# Power.net
KiCad netlist of a schematic drawn in Altium Designer
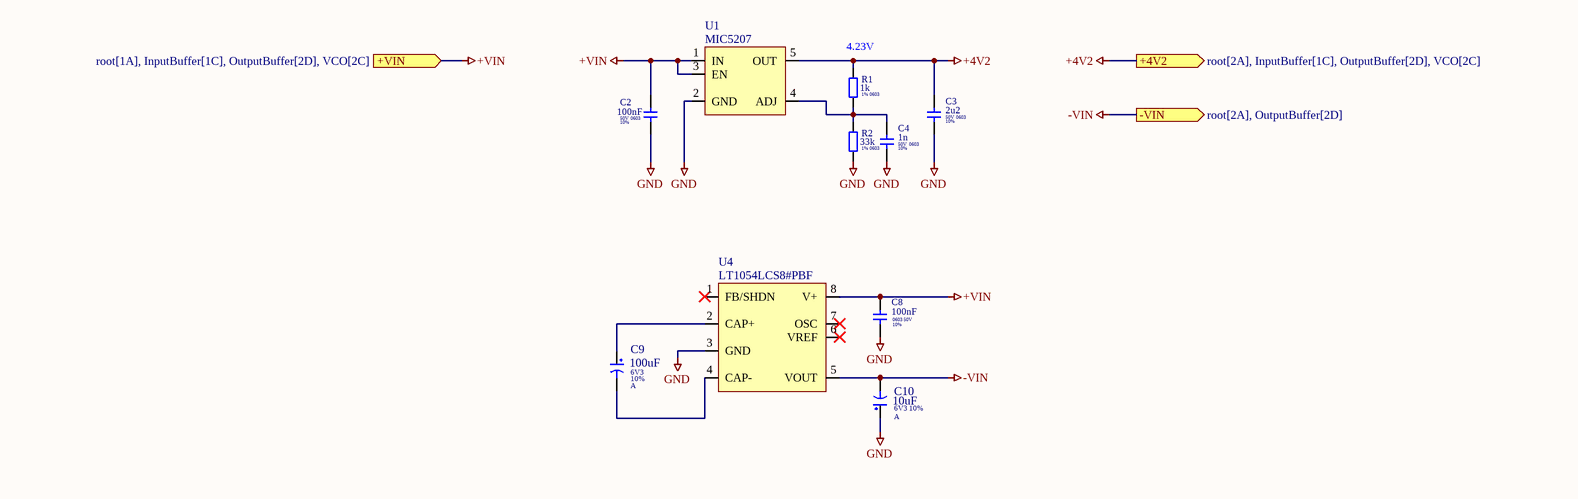
[diagram p0: Power.SchDoc]

(export (version "E")
  (design (tool "Eeschema 10.0.6"))
  (components
    (comp (ref "C2")
      (value "100nF")
      (footprint "CAPC1608X06M")
      (fields
        (field (name "VOLTAGE") "50V")
        (field (name "TOLERANT") "10%")
        (field (name "PACKAGE") "0603")
        (field (name "Comment") "100nF/50V")
      )
      (libsource (lib "Falcon-SchMain-Lib") (part "C"))
    )
    (comp (ref "C3")
      (value "2u2")
      (footprint "CAPC1608X06M")
      (fields
        (field (name "VOLTAGE") "50V")
        (field (name "TOLERANT") "10%")
        (field (name "PACKAGE") "0603")
        (field (name "Comment") "2u2/50V")
      )
      (libsource (lib "Falcon-SchMain-Lib") (part "C"))
    )
    (comp (ref "C4")
      (value "1n")
      (footprint "CAPC1608X06M")
      (fields
        (field (name "VOLTAGE") "50V")
        (field (name "TOLERANT") "10%")
        (field (name "PACKAGE") "0603")
        (field (name "Comment") "1n/50V")
      )
      (libsource (lib "Falcon-SchMain-Lib") (part "C"))
    )
    (comp (ref "C8")
      (value "100nF")
      (footprint "CAPC1608X06M")
      (fields
        (field (name "VOLTAGE") "50V")
        (field (name "TOLERANT") "10%")
        (field (name "PACKAGE") "0603")
        (field (name "Comment") "100nF/50V")
      )
      (libsource (lib "Falcon-SchMain-Lib") (part "C"))
    )
    (comp (ref "C9")
      (value "100uF")
      (footprint "CAPMP3217X16L")
      (fields
        (field (name "VOLTAGE") "6V3")
        (field (name "PACKAGE") "A")
        (field (name "TOLERANT") "10%")
        (field (name "Comment") "100uF/6V3")
      )
      (libsource (lib "Falcon-SchMain-Lib") (part "C_TANTAL"))
    )
    (comp (ref "C10")
      (value "10uF")
      (footprint "CAPMP3217X16L")
      (fields
        (field (name "VOLTAGE") "6V3")
        (field (name "PACKAGE") "A")
        (field (name "TOLERANT") "10%")
        (field (name "Comment") "10uF/6V3")
      )
      (libsource (lib "Falcon-SchMain-Lib") (part "C_TANTAL"))
    )
    (comp (ref "R1")
      (value "1k")
      (footprint "RESC1608X06L")
      (fields
        (field (name "PACKAGE") "0603")
        (field (name "TOLERANCE") "1%")
        (field (name "Comment") "1k 1%")
      )
      (libsource (lib "Falcon-SchMain-Lib") (part "R"))
    )
    (comp (ref "R2")
      (value "33k")
      (footprint "RESC1608X06L")
      (fields
        (field (name "PACKAGE") "0603")
        (field (name "TOLERANCE") "1%")
        (field (name "Comment") "33k 1%")
      )
      (libsource (lib "Falcon-SchMain-Lib") (part "R"))
    )
    (comp (ref "U1")
      (value "MIC5207")
      (footprint "SOT95P245X110-5M")
      (description "180 mA Low-Noise LDO Regulator")
      (libsource (lib "Falcon-SchMain-Lib") (part "MIC5207YM5-TR"))
    )
    (comp (ref "U4")
      (value "LT1054LCS8#PBF")
      (footprint "SOIC-8")
      (description "Switched-Capacitor Voltage\r\nConverter with Regulator")
      (fields (field (name "MANUFACTURER") "AnalogDevices"))
      (libsource (lib "Falcon-SchMain-Lib") (part "LT1054"))
    )
  )
  (nets
    (net (code "1") (name "+4V2") (class "Default")
      (node (ref "C3") (pin "2") (pinfunction "2_2") (pintype "passive"))
      (node (ref "R1") (pin "2") (pinfunction "2_2") (pintype "passive"))
      (node (ref "U1") (pin "5") (pinfunction "OUT_5") (pintype "power_in"))
    )
    (net (code "2") (name "+VIN") (class "Default")
      (node (ref "C2") (pin "2") (pinfunction "2_2") (pintype "passive"))
      (node (ref "C8") (pin "2") (pinfunction "2_2") (pintype "passive"))
      (node (ref "U1") (pin "1") (pinfunction "IN_1") (pintype "power_in"))
      (node (ref "U1") (pin "3") (pinfunction "EN_3") (pintype "power_in"))
      (node (ref "U4") (pin "8") (pinfunction "V+_8") (pintype "power_in"))
    )
    (net (code "3") (name "-VIN") (class "Default")
      (node (ref "C10") (pin "2") (pinfunction "2_2") (pintype "passive"))
      (node (ref "U4") (pin "5") (pinfunction "VOUT_5") (pintype "power_in"))
    )
    (net (code "4") (name "GND") (class "Default")
      (node (ref "C10") (pin "1") (pinfunction "1_1") (pintype "passive"))
      (node (ref "C2") (pin "1") (pinfunction "1_1") (pintype "passive"))
      (node (ref "C3") (pin "1") (pinfunction "1_1") (pintype "passive"))
      (node (ref "C4") (pin "1") (pinfunction "1_1") (pintype "passive"))
      (node (ref "C8") (pin "1") (pinfunction "1_1") (pintype "passive"))
      (node (ref "R2") (pin "1") (pinfunction "1_1") (pintype "passive"))
      (node (ref "U1") (pin "2") (pinfunction "GND_2") (pintype "power_in"))
      (node (ref "U4") (pin "3") (pinfunction "GND_3") (pintype "power_in"))
    )
    (net (code "5") (name "Net-(U1-ADJ)") (class "Default")
      (node (ref "C4") (pin "2") (pinfunction "2_2") (pintype "passive"))
      (node (ref "R1") (pin "1") (pinfunction "1_1") (pintype "passive"))
      (node (ref "R2") (pin "2") (pinfunction "2_2") (pintype "passive"))
      (node (ref "U1") (pin "4") (pinfunction "ADJ_4") (pintype "power_in"))
    )
    (net (code "6") (name "Net-(U4-CAP+)") (class "Default")
      (node (ref "C9") (pin "1") (pinfunction "1_1") (pintype "passive"))
      (node (ref "U4") (pin "2") (pinfunction "CAP+_2") (pintype "power_in"))
    )
    (net (code "7") (name "Net-(U4-CAP-)") (class "Default")
      (node (ref "C9") (pin "2") (pinfunction "2_2") (pintype "passive"))
      (node (ref "U4") (pin "4") (pinfunction "CAP-_4") (pintype "power_in"))
    )
    (net (code "8") (name "unconnected-(U4-FB{slash}SHDN-Pad1)") (class "Default")
      (node (ref "U4") (pin "1") (pinfunction "FB/SHDN_1") (pintype "power_in+no_connect"))
    )
    (net (code "9") (name "unconnected-(U4-OSC-Pad7)") (class "Default")
      (node (ref "U4") (pin "7") (pinfunction "OSC_7") (pintype "power_in+no_connect"))
    )
    (net (code "10") (name "unconnected-(U4-VREF-Pad6)") (class "Default")
      (node (ref "U4") (pin "6") (pinfunction "VREF_6") (pintype "power_in+no_connect"))
    )
  )
)
